# AuxTalon_LoadSwitch.net
KiCad netlist of a schematic drawn in EAGLE
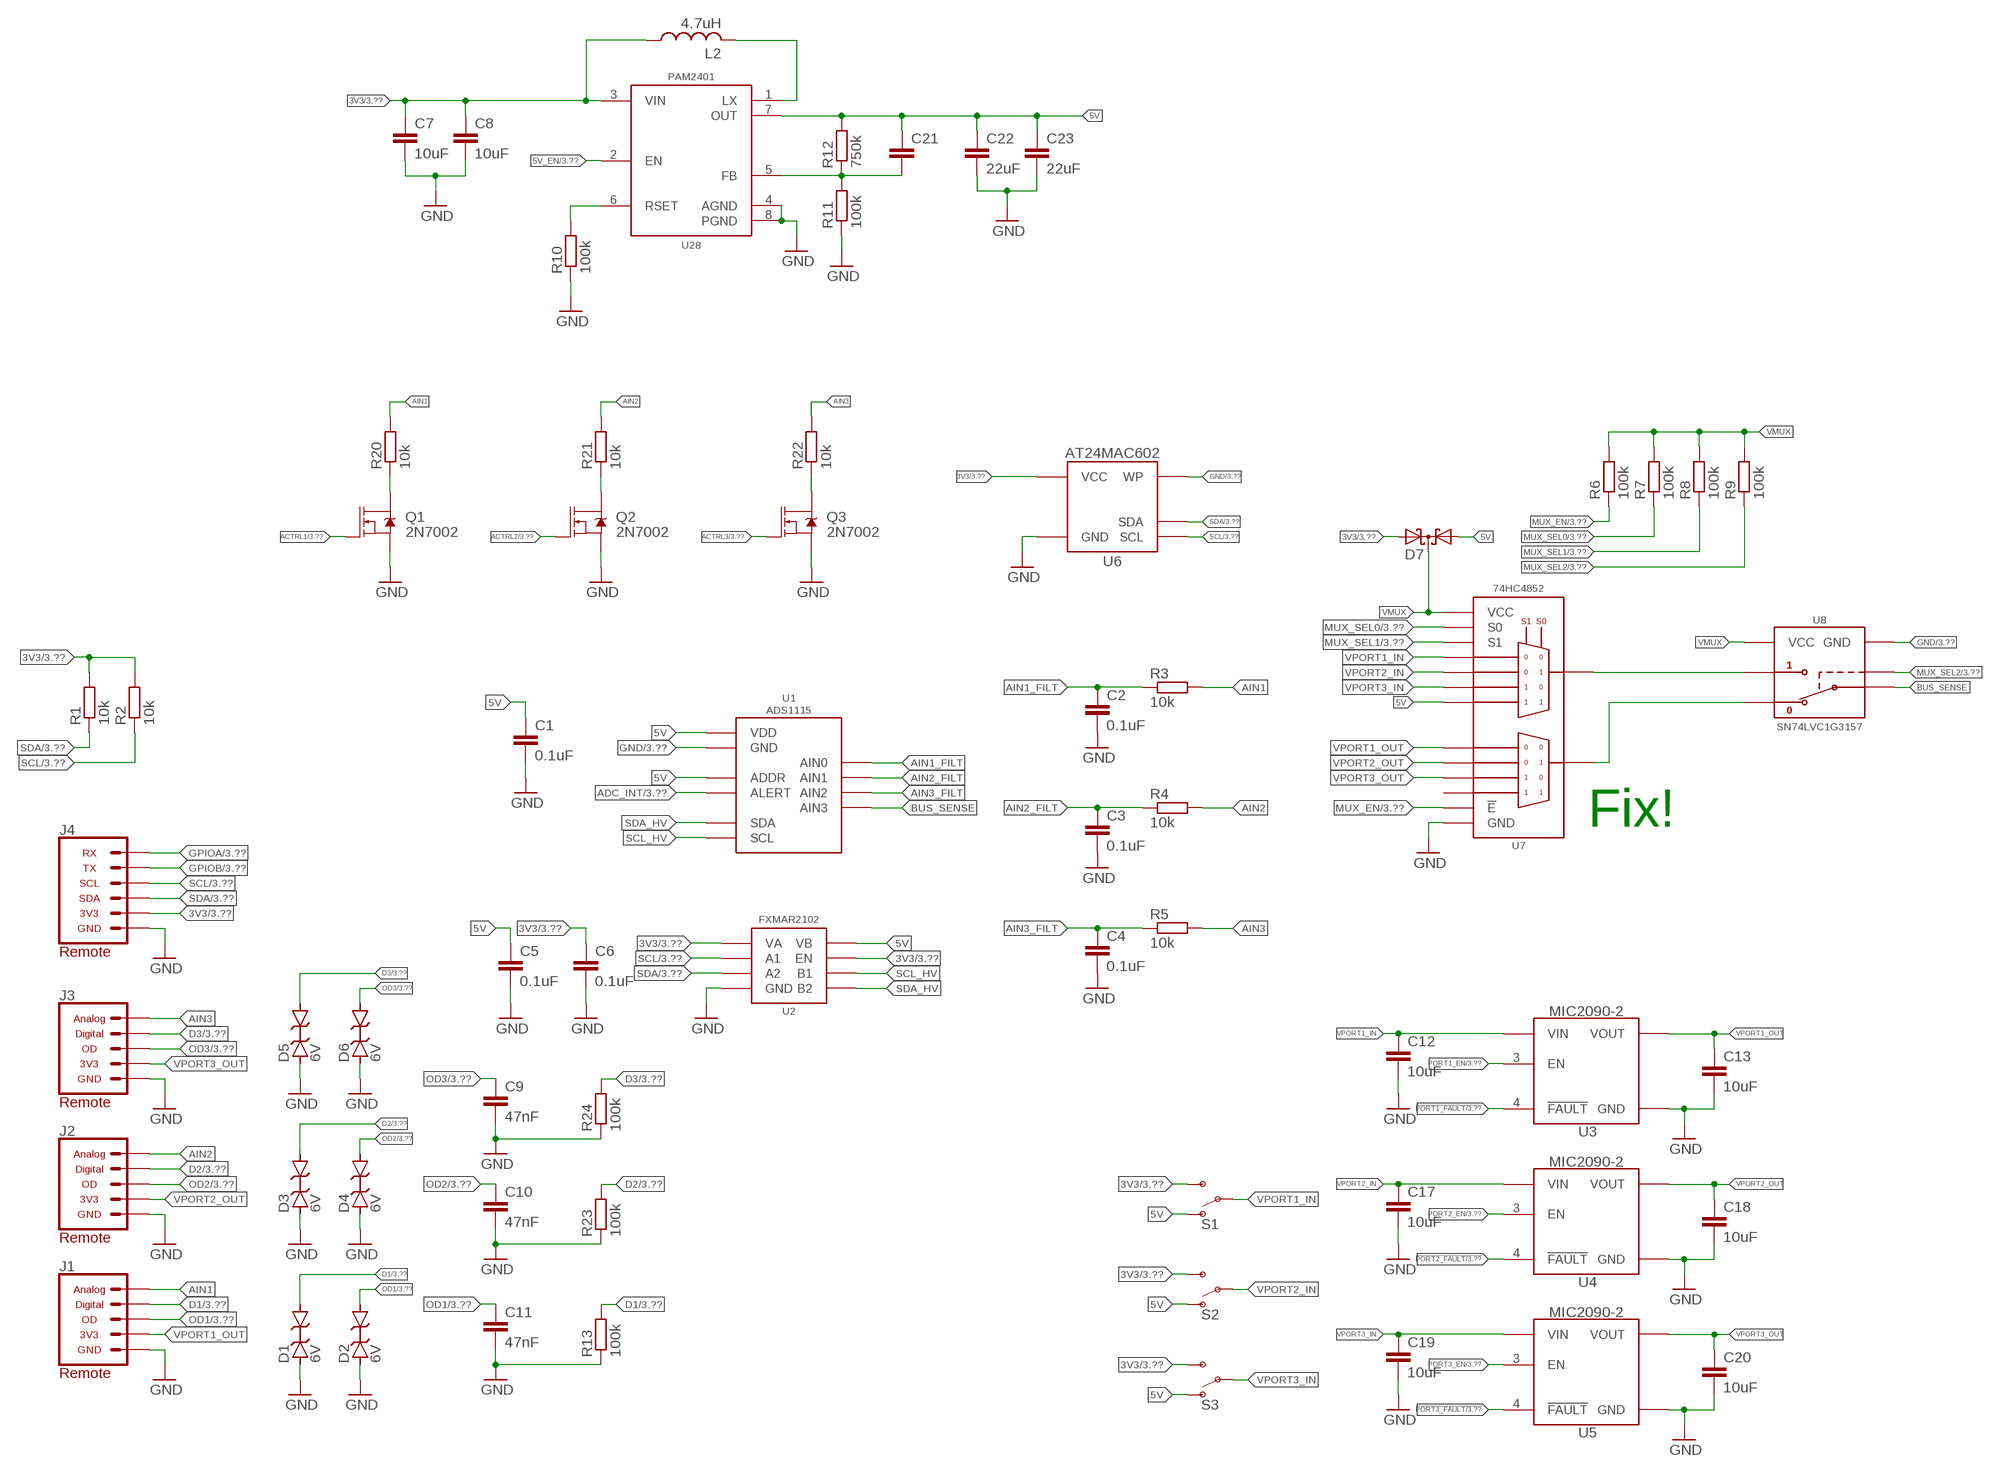
[diagram p0: schematic, sheet 2]
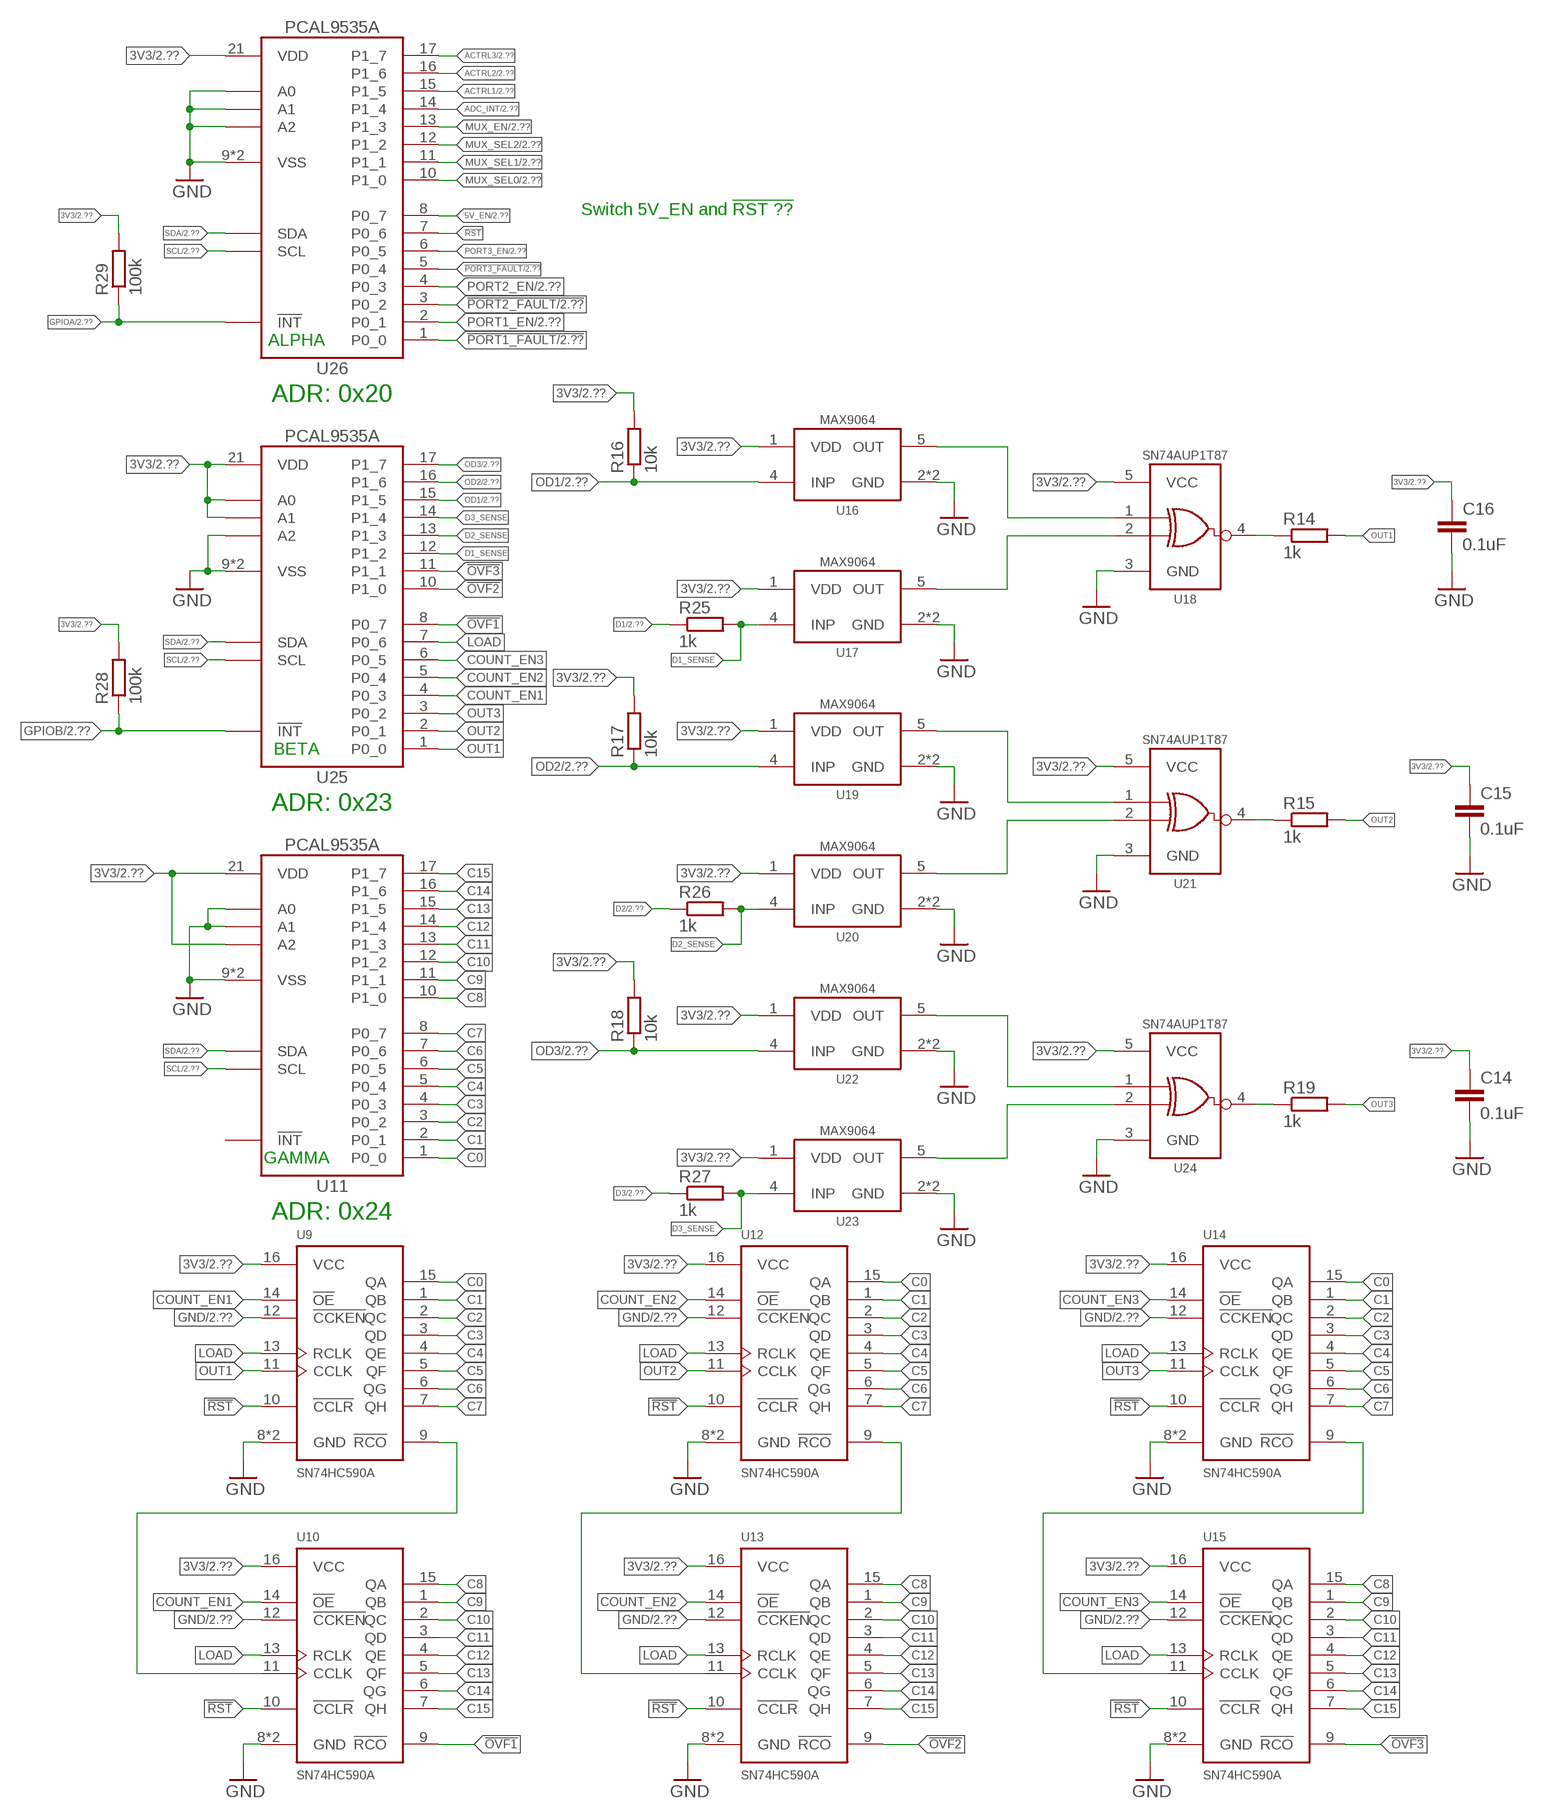
[diagram p1: schematic, sheet 3]

(export (version "E")
  (design (tool "Eeschema 10.0.6"))
  (components
    (comp (ref "C1")
      (value "0.1uF")
      (footprint "eagle-import:C0402")
      (fields (field (name "MF") "Murata") (field (name "MPN") "GCM155R71C104KA55D"))
      (libsource (lib "eagle-import") (part "C-EUC04020.1UF"))
    )
    (comp (ref "C2")
      (value "0.1uF")
      (footprint "eagle-import:C0805")
      (fields (field (name "MF") "Kemet") (field (name "MPN") "C0805C104M3RACTU"))
      (libsource (lib "eagle-import") (part "C-EUC08050.1UF"))
    )
    (comp (ref "C3")
      (value "0.1uF")
      (footprint "eagle-import:C0805")
      (fields (field (name "MF") "Kemet") (field (name "MPN") "C0805C104M3RACTU"))
      (libsource (lib "eagle-import") (part "C-EUC08050.1UF"))
    )
    (comp (ref "C4")
      (value "0.1uF")
      (footprint "eagle-import:C0805")
      (fields (field (name "MF") "Kemet") (field (name "MPN") "C0805C104M3RACTU"))
      (libsource (lib "eagle-import") (part "C-EUC08050.1UF"))
    )
    (comp (ref "C5")
      (value "0.1uF")
      (footprint "eagle-import:C0402")
      (fields (field (name "MF") "Murata") (field (name "MPN") "GCM155R71C104KA55D"))
      (libsource (lib "eagle-import") (part "C-EUC04020.1UF"))
    )
    (comp (ref "C6")
      (value "0.1uF")
      (footprint "eagle-import:C0402")
      (fields (field (name "MF") "Murata") (field (name "MPN") "GCM155R71C104KA55D"))
      (libsource (lib "eagle-import") (part "C-EUC04020.1UF"))
    )
    (comp (ref "C7")
      (value "10uF")
      (footprint "eagle-import:C0805")
      (fields (field (name "MF") "Murata") (field (name "MPN") "GRM21BR61C106KE15K"))
      (libsource (lib "eagle-import") (part "C-EUC080510UF"))
    )
    (comp (ref "C8")
      (value "10uF")
      (footprint "eagle-import:C0805")
      (fields (field (name "MF") "Murata") (field (name "MPN") "GRM21BR61C106KE15K"))
      (libsource (lib "eagle-import") (part "C-EUC080510UF"))
    )
    (comp (ref "C9")
      (value "47nF")
      (footprint "eagle-import:C0402")
      (fields (field (name "MF") "Murata") (field (name "MPN") "GRM155R71E473KA88D"))
      (libsource (lib "eagle-import") (part "C-EUC040247NF"))
    )
    (comp (ref "C10")
      (value "47nF")
      (footprint "eagle-import:C0402")
      (fields (field (name "MF") "Murata") (field (name "MPN") "GRM155R71E473KA88D"))
      (libsource (lib "eagle-import") (part "C-EUC040247NF"))
    )
    (comp (ref "C11")
      (value "47nF")
      (footprint "eagle-import:C0402")
      (fields (field (name "MF") "Murata") (field (name "MPN") "GRM155R71E473KA88D"))
      (libsource (lib "eagle-import") (part "C-EUC040247NF"))
    )
    (comp (ref "C12")
      (value "10uF")
      (footprint "eagle-import:C0805")
      (fields (field (name "MF") "Murata") (field (name "MPN") "GRM21BR61C106KE15K"))
      (libsource (lib "eagle-import") (part "C-EUC080510UF"))
    )
    (comp (ref "C13")
      (value "10uF")
      (footprint "eagle-import:C0603")
      (fields (field (name "MF") "Murata") (field (name "MPN") "GRM188R61C106KAALD"))
      (libsource (lib "eagle-import") (part "C-EUC060310UF"))
    )
    (comp (ref "C17")
      (value "10uF")
      (footprint "eagle-import:C0805")
      (fields (field (name "MF") "Murata") (field (name "MPN") "GRM21BR61C106KE15K"))
      (libsource (lib "eagle-import") (part "C-EUC080510UF"))
    )
    (comp (ref "C18")
      (value "10uF")
      (footprint "eagle-import:C0603")
      (fields (field (name "MF") "Murata") (field (name "MPN") "GRM188R61C106KAALD"))
      (libsource (lib "eagle-import") (part "C-EUC060310UF"))
    )
    (comp (ref "C19")
      (value "10uF")
      (footprint "eagle-import:C0805")
      (fields (field (name "MF") "Murata") (field (name "MPN") "GRM21BR61C106KE15K"))
      (libsource (lib "eagle-import") (part "C-EUC080510UF"))
    )
    (comp (ref "C20")
      (value "10uF")
      (footprint "eagle-import:C0603")
      (fields (field (name "MF") "Murata") (field (name "MPN") "GRM188R61C106KAALD"))
      (libsource (lib "eagle-import") (part "C-EUC060310UF"))
    )
    (comp (ref "C21")
      (value "C-EUC0402")
      (footprint "eagle-import:C0402")
      (fields (field (name "DIGIKEY") "DNP") (field (name "MF") "N/A") (field (name "MPN") "DNP"))
      (libsource (lib "eagle-import") (part "C-EUC0402"))
    )
    (comp (ref "C22")
      (value "22uF")
      (footprint "eagle-import:C0805")
      (fields (field (name "MF") "Murata") (field (name "MPN") "GRM219R61C226ME15L"))
      (libsource (lib "eagle-import") (part "C-EUC080522UF"))
    )
    (comp (ref "C23")
      (value "22uF")
      (footprint "eagle-import:C0805")
      (fields (field (name "MF") "Murata") (field (name "MPN") "GRM219R61C226ME15L"))
      (libsource (lib "eagle-import") (part "C-EUC080522UF"))
    )
    (comp (ref "D1")
      (value "6V")
      (footprint "eagle-import:D0402")
      (fields (field (name "MF") "Diodes Inc") (field (name "MPN") "D5V0L1B2LP4-7B"))
      (libsource (lib "eagle-import") (part "DIODE_ESD_BI_0402_D5V0L1"))
    )
    (comp (ref "D2")
      (value "6V")
      (footprint "eagle-import:D0402")
      (fields (field (name "MF") "Diodes Inc") (field (name "MPN") "D5V0L1B2LP4-7B"))
      (libsource (lib "eagle-import") (part "DIODE_ESD_BI_0402_D5V0L1"))
    )
    (comp (ref "D3")
      (value "6V")
      (footprint "eagle-import:D0402")
      (fields (field (name "MF") "Diodes Inc") (field (name "MPN") "D5V0L1B2LP4-7B"))
      (libsource (lib "eagle-import") (part "DIODE_ESD_BI_0402_D5V0L1"))
    )
    (comp (ref "D4")
      (value "6V")
      (footprint "eagle-import:D0402")
      (fields (field (name "MF") "Diodes Inc") (field (name "MPN") "D5V0L1B2LP4-7B"))
      (libsource (lib "eagle-import") (part "DIODE_ESD_BI_0402_D5V0L1"))
    )
    (comp (ref "D5")
      (value "6V")
      (footprint "eagle-import:D0402")
      (fields (field (name "MF") "Diodes Inc") (field (name "MPN") "D5V0L1B2LP4-7B"))
      (libsource (lib "eagle-import") (part "DIODE_ESD_BI_0402_D5V0L1"))
    )
    (comp (ref "D6")
      (value "6V")
      (footprint "eagle-import:D0402")
      (fields (field (name "MF") "Diodes Inc") (field (name "MPN") "D5V0L1B2LP4-7B"))
      (libsource (lib "eagle-import") (part "DIODE_ESD_BI_0402_D5V0L1"))
    )
    (comp (ref "D7")
      (value "DIODE_CCBAT54CSOT23")
      (footprint "eagle-import:SOT23-3")
      (fields (field (name "MF") "ON Semiconductor") (field (name "MPN") "BAT54CLT1G"))
      (libsource (lib "eagle-import") (part "DIODE_CCSOT23BAT54C"))
    )
    (comp (ref "J1")
      (value "CONN_AUX_M12_REMOTE")
      (footprint "eagle-import:1X05_M12_TE_T41410")
      (fields (field (name "DISP") "Remote") (field (name "MF") "TE") (field (name "MPN") "T4141012051-000"))
      (libsource (lib "eagle-import") (part "CONN_AUX_M12_REMOTE"))
    )
    (comp (ref "J2")
      (value "CONN_AUX_M12_REMOTE")
      (footprint "eagle-import:1X05_M12_TE_T41410")
      (fields (field (name "DISP") "Remote") (field (name "MF") "TE") (field (name "MPN") "T4141012051-000"))
      (libsource (lib "eagle-import") (part "CONN_AUX_M12_REMOTE"))
    )
    (comp (ref "J3")
      (value "CONN_AUX_M12_REMOTE")
      (footprint "eagle-import:1X05_M12_TE_T41410")
      (fields (field (name "DISP") "Remote") (field (name "MF") "TE") (field (name "MPN") "T4141012051-000"))
      (libsource (lib "eagle-import") (part "CONN_AUX_M12_REMOTE"))
    )
    (comp (ref "J4")
      (value "CONN_TALON_REMOTE")
      (footprint "eagle-import:1X06_MICROLOCKPLUS")
      (fields (field (name "DISP") "Remote") (field (name "MF") "Molex") (field (name "MPN") "2059570671"))
      (libsource (lib "eagle-import") (part "CONN_TALON_REMOTE"))
    )
    (comp (ref "L2")
      (value "4.7uH")
      (footprint "eagle-import:WE-MAPI(2.5X2)")
      (fields (field (name "MF") "Wurth") (field (name "MPN") "74438323047"))
      (libsource (lib "eagle-import") (part "INDUCTOR_MAPI_2.5X2"))
    )
    (comp (ref "Q1")
      (value "2N7002")
      (footprint "eagle-import:SOT23-3")
      (fields (field (name "MF") "Nexperia") (field (name "MPN") "2N7002P,215"))
      (libsource (lib "eagle-import") (part "MOSFET-NCH-2N7002P"))
    )
    (comp (ref "Q2")
      (value "2N7002")
      (footprint "eagle-import:SOT23-3")
      (fields (field (name "MF") "Nexperia") (field (name "MPN") "2N7002P,215"))
      (libsource (lib "eagle-import") (part "MOSFET-NCH-2N7002P"))
    )
    (comp (ref "Q3")
      (value "2N7002")
      (footprint "eagle-import:SOT23-3")
      (fields (field (name "MF") "Nexperia") (field (name "MPN") "2N7002P,215"))
      (libsource (lib "eagle-import") (part "MOSFET-NCH-2N7002P"))
    )
    (comp (ref "R1")
      (value "10k")
      (footprint "eagle-import:R0402")
      (fields (field (name "MF") "Yageo") (field (name "MPN") "RC0402FR-0710KL"))
      (libsource (lib "eagle-import") (part "R-EU_R040210K"))
    )
    (comp (ref "R2")
      (value "10k")
      (footprint "eagle-import:R0402")
      (fields (field (name "MF") "Yageo") (field (name "MPN") "RC0402FR-0710KL"))
      (libsource (lib "eagle-import") (part "R-EU_R040210K"))
    )
    (comp (ref "R3")
      (value "10k")
      (footprint "eagle-import:R0402")
      (fields (field (name "MF") "Yageo") (field (name "MPN") "RC0402FR-0710KL"))
      (libsource (lib "eagle-import") (part "R-EU_R040210K"))
    )
    (comp (ref "R4")
      (value "10k")
      (footprint "eagle-import:R0402")
      (fields (field (name "MF") "Yageo") (field (name "MPN") "RC0402FR-0710KL"))
      (libsource (lib "eagle-import") (part "R-EU_R040210K"))
    )
    (comp (ref "R5")
      (value "10k")
      (footprint "eagle-import:R0402")
      (fields (field (name "MF") "Yageo") (field (name "MPN") "RC0402FR-0710KL"))
      (libsource (lib "eagle-import") (part "R-EU_R040210K"))
    )
    (comp (ref "R6")
      (value "100k")
      (footprint "eagle-import:R0402")
      (fields (field (name "MF") "Yageo") (field (name "MPN") "RC0402FR-07100KL"))
      (libsource (lib "eagle-import") (part "R-EU_R0402100K"))
    )
    (comp (ref "R7")
      (value "100k")
      (footprint "eagle-import:R0402")
      (fields (field (name "MF") "Yageo") (field (name "MPN") "RC0402FR-07100KL"))
      (libsource (lib "eagle-import") (part "R-EU_R0402100K"))
    )
    (comp (ref "R8")
      (value "100k")
      (footprint "eagle-import:R0402")
      (fields (field (name "MF") "Yageo") (field (name "MPN") "RC0402FR-07100KL"))
      (libsource (lib "eagle-import") (part "R-EU_R0402100K"))
    )
    (comp (ref "R9")
      (value "100k")
      (footprint "eagle-import:R0402")
      (fields (field (name "MF") "Yageo") (field (name "MPN") "RC0402FR-07100KL"))
      (libsource (lib "eagle-import") (part "R-EU_R0402100K"))
    )
    (comp (ref "R10")
      (value "100k")
      (footprint "eagle-import:R0603")
      (fields (field (name "MF") "Yageo") (field (name "MPN") "RC0603FR-07100KL"))
      (libsource (lib "eagle-import") (part "R-EU_R0603100K"))
    )
    (comp (ref "R11")
      (value "100k")
      (footprint "eagle-import:R0603")
      (fields (field (name "MF") "Yageo") (field (name "MPN") "RC0603FR-07100KL"))
      (libsource (lib "eagle-import") (part "R-EU_R0603100K"))
    )
    (comp (ref "R12")
      (value "750k")
      (footprint "eagle-import:R0603")
      (fields (field (name "MF") "Yageo") (field (name "MPN") "RC0603FR-07750KL"))
      (libsource (lib "eagle-import") (part "R-EU_R0603750K"))
    )
    (comp (ref "R13")
      (value "100k")
      (footprint "eagle-import:R0402")
      (fields (field (name "MF") "Yageo") (field (name "MPN") "RC0402FR-07100KL"))
      (libsource (lib "eagle-import") (part "R-EU_R0402100K"))
    )
    (comp (ref "R20")
      (value "10k")
      (footprint "eagle-import:R0402")
      (fields (field (name "MF") "Yageo") (field (name "MPN") "RC0402FR-0710KL"))
      (libsource (lib "eagle-import") (part "R-EU_R040210K"))
    )
    (comp (ref "R21")
      (value "10k")
      (footprint "eagle-import:R0402")
      (fields (field (name "MF") "Yageo") (field (name "MPN") "RC0402FR-0710KL"))
      (libsource (lib "eagle-import") (part "R-EU_R040210K"))
    )
    (comp (ref "R22")
      (value "10k")
      (footprint "eagle-import:R0402")
      (fields (field (name "MF") "Yageo") (field (name "MPN") "RC0402FR-0710KL"))
      (libsource (lib "eagle-import") (part "R-EU_R040210K"))
    )
    (comp (ref "R23")
      (value "100k")
      (footprint "eagle-import:R0402")
      (fields (field (name "MF") "Yageo") (field (name "MPN") "RC0402FR-07100KL"))
      (libsource (lib "eagle-import") (part "R-EU_R0402100K"))
    )
    (comp (ref "R24")
      (value "100k")
      (footprint "eagle-import:R0402")
      (fields (field (name "MF") "Yageo") (field (name "MPN") "RC0402FR-07100KL"))
      (libsource (lib "eagle-import") (part "R-EU_R0402100K"))
    )
    (comp (ref "S1")
      (value "SPDTCAS-120A1")
      (footprint "eagle-import:CAS-120A1")
      (fields (field (name "MF") "Nidec Copal") (field (name "MPN") "CAS-120TA"))
      (libsource (lib "eagle-import") (part "SPDTCAS-120A1"))
    )
    (comp (ref "S2")
      (value "SPDTCAS-120A1")
      (footprint "eagle-import:CAS-120A1")
      (fields (field (name "MF") "Nidec Copal") (field (name "MPN") "CAS-120TA"))
      (libsource (lib "eagle-import") (part "SPDTCAS-120A1"))
    )
    (comp (ref "S3")
      (value "SPDTCAS-120A1")
      (footprint "eagle-import:CAS-120A1")
      (fields (field (name "MF") "Nidec Copal") (field (name "MPN") "CAS-120TA"))
      (libsource (lib "eagle-import") (part "SPDTCAS-120A1"))
    )
    (comp (ref "U1")
      (value "ADS1115")
      (footprint "eagle-import:VSSOP_10")
      (fields (field (name "MF") "TI") (field (name "MPN") "ADS1115IDGSR"))
      (libsource (lib "eagle-import") (part "ADS1115"))
    )
    (comp (ref "U2")
      (value "FXMAR2102UMLP")
      (footprint "eagle-import:UQFN-8_1.4X1.2")
      (fields
        (field (name "DISP") "FXMAR2102")
        (field (name "MF") "OnSemi")
        (field (name "MPN") "FXMAR2102UMX-F106")
      )
      (libsource (lib "eagle-import") (part "FXMAR2102UMLP"))
    )
    (comp (ref "U3")
      (value "MIC2090-2")
      (footprint "eagle-import:SOT23-5")
      (fields
        (field (name "DISP") "MIC2090-2")
        (field (name "MF") "Microchip")
        (field (name "MPN") "MIC2090-2YM5-TR")
      )
      (libsource (lib "eagle-import") (part "MIC2090-2"))
    )
    (comp (ref "U4")
      (value "MIC2090-2")
      (footprint "eagle-import:SOT23-5")
      (fields
        (field (name "DISP") "MIC2090-2")
        (field (name "MF") "Microchip")
        (field (name "MPN") "MIC2090-2YM5-TR")
      )
      (libsource (lib "eagle-import") (part "MIC2090-2"))
    )
    (comp (ref "U5")
      (value "MIC2090-2")
      (footprint "eagle-import:SOT23-5")
      (fields
        (field (name "DISP") "MIC2090-2")
        (field (name "MF") "Microchip")
        (field (name "MPN") "MIC2090-2YM5-TR")
      )
      (libsource (lib "eagle-import") (part "MIC2090-2"))
    )
    (comp (ref "U6")
      (value "AT24MAC602SOT23")
      (footprint "eagle-import:SOT23-5")
      (fields
        (field (name "DISP") "AT24MAC602")
        (field (name "MF") "Microchip")
        (field (name "MPN") "AT24MAC602-STUM-T")
      )
      (libsource (lib "eagle-import") (part "AT24MAC02SOT236"))
    )
    (comp (ref "U7")
      (value "74HC4852")
      (footprint "eagle-import:VQFN-16")
      (fields
        (field (name "DISP") "74HC4852")
        (field (name "MF") "Nexperia")
        (field (name "MPN") "74HC4852BQ-Q100,11")
      )
      (libsource (lib "eagle-import") (part "74HC4852"))
    )
    (comp (ref "U8")
      (value "SN74LVC1G3157SC70")
      (footprint "eagle-import:DCK_R-PDSO-G6")
      (fields
        (field (name "DISP") "SN74LVC1G3157")
        (field (name "MF") "TI")
        (field (name "MPN") "SN74LVC1G3157DCKR")
      )
      (libsource (lib "eagle-import") (part "SN74LVC1G3157SC70"))
    )
    (comp (ref "U28")
      (value "PAM2401MSOP")
      (footprint "eagle-import:MSOP_8")
      (fields (field (name "MF") "Diodes Inc") (field (name "MPN") "PAM2401SCADJ"))
      (libsource (lib "eagle-import") (part "PAM2401MSOP"))
    )
    (comp (ref "C14")
      (value "0.1uF")
      (footprint "eagle-import:C0402")
      (fields (field (name "MF") "Murata") (field (name "MPN") "GCM155R71C104KA55D"))
      (libsource (lib "eagle-import") (part "C-EUC04020.1UF"))
    )
    (comp (ref "C15")
      (value "0.1uF")
      (footprint "eagle-import:C0402")
      (fields (field (name "MF") "Murata") (field (name "MPN") "GCM155R71C104KA55D"))
      (libsource (lib "eagle-import") (part "C-EUC04020.1UF"))
    )
    (comp (ref "C16")
      (value "0.1uF")
      (footprint "eagle-import:C0402")
      (fields (field (name "MF") "Murata") (field (name "MPN") "GCM155R71C104KA55D"))
      (libsource (lib "eagle-import") (part "C-EUC04020.1UF"))
    )
    (comp (ref "R14")
      (value "1k")
      (footprint "eagle-import:R0402")
      (fields (field (name "MF") "Yageo") (field (name "MPN") "RC0402FR-071KL"))
      (libsource (lib "eagle-import") (part "R-EU_R04021K"))
    )
    (comp (ref "R15")
      (value "1k")
      (footprint "eagle-import:R0402")
      (fields (field (name "MF") "Yageo") (field (name "MPN") "RC0402FR-071KL"))
      (libsource (lib "eagle-import") (part "R-EU_R04021K"))
    )
    (comp (ref "R16")
      (value "10k")
      (footprint "eagle-import:R0402")
      (fields (field (name "MF") "Yageo") (field (name "MPN") "RC0402FR-0710KL"))
      (libsource (lib "eagle-import") (part "R-EU_R040210K"))
    )
    (comp (ref "R17")
      (value "10k")
      (footprint "eagle-import:R0402")
      (fields (field (name "MF") "Yageo") (field (name "MPN") "RC0402FR-0710KL"))
      (libsource (lib "eagle-import") (part "R-EU_R040210K"))
    )
    (comp (ref "R18")
      (value "10k")
      (footprint "eagle-import:R0402")
      (fields (field (name "MF") "Yageo") (field (name "MPN") "RC0402FR-0710KL"))
      (libsource (lib "eagle-import") (part "R-EU_R040210K"))
    )
    (comp (ref "R19")
      (value "1k")
      (footprint "eagle-import:R0402")
      (fields (field (name "MF") "Yageo") (field (name "MPN") "RC0402FR-071KL"))
      (libsource (lib "eagle-import") (part "R-EU_R04021K"))
    )
    (comp (ref "R25")
      (value "1k")
      (footprint "eagle-import:R0402")
      (fields (field (name "MF") "Yageo") (field (name "MPN") "RC0402FR-071KL"))
      (libsource (lib "eagle-import") (part "R-EU_R04021K"))
    )
    (comp (ref "R26")
      (value "1k")
      (footprint "eagle-import:R0402")
      (fields (field (name "MF") "Yageo") (field (name "MPN") "RC0402FR-071KL"))
      (libsource (lib "eagle-import") (part "R-EU_R04021K"))
    )
    (comp (ref "R27")
      (value "1k")
      (footprint "eagle-import:R0402")
      (fields (field (name "MF") "Yageo") (field (name "MPN") "RC0402FR-071KL"))
      (libsource (lib "eagle-import") (part "R-EU_R04021K"))
    )
    (comp (ref "R28")
      (value "100k")
      (footprint "eagle-import:R0402")
      (fields (field (name "MF") "Yageo") (field (name "MPN") "RC0402FR-07100KL"))
      (libsource (lib "eagle-import") (part "R-EU_R0402100K"))
    )
    (comp (ref "R29")
      (value "100k")
      (footprint "eagle-import:R0402")
      (fields (field (name "MF") "Yageo") (field (name "MPN") "RC0402FR-07100KL"))
      (libsource (lib "eagle-import") (part "R-EU_R0402100K"))
    )
    (comp (ref "U9")
      (value "SN74HC590AVQFN")
      (footprint "eagle-import:VQFN-16")
      (fields (field (name "MF") "Nexperia") (field (name "MPN") "74HC590BQ,115"))
      (libsource (lib "eagle-import") (part "SN74HC590AVQFN"))
    )
    (comp (ref "U10")
      (value "SN74HC590AVQFN")
      (footprint "eagle-import:VQFN-16")
      (fields (field (name "MF") "Nexperia") (field (name "MPN") "74HC590BQ,115"))
      (libsource (lib "eagle-import") (part "SN74HC590AVQFN"))
    )
    (comp (ref "U11")
      (value "PCAL9535AQFN")
      (footprint "eagle-import:QFN24")
      (fields
        (field (name "DISP") "PCAL9535A")
        (field (name "MF") "NXP")
        (field (name "MPN") "PCAL9535AHF,128")
      )
      (libsource (lib "eagle-import") (part "PCAL955AQFN3"))
    )
    (comp (ref "U12")
      (value "SN74HC590AVQFN")
      (footprint "eagle-import:VQFN-16")
      (fields (field (name "MF") "Nexperia") (field (name "MPN") "74HC590BQ,115"))
      (libsource (lib "eagle-import") (part "SN74HC590AVQFN"))
    )
    (comp (ref "U13")
      (value "SN74HC590AVQFN")
      (footprint "eagle-import:VQFN-16")
      (fields (field (name "MF") "Nexperia") (field (name "MPN") "74HC590BQ,115"))
      (libsource (lib "eagle-import") (part "SN74HC590AVQFN"))
    )
    (comp (ref "U14")
      (value "SN74HC590AVQFN")
      (footprint "eagle-import:VQFN-16")
      (fields (field (name "MF") "Nexperia") (field (name "MPN") "74HC590BQ,115"))
      (libsource (lib "eagle-import") (part "SN74HC590AVQFN"))
    )
    (comp (ref "U15")
      (value "SN74HC590AVQFN")
      (footprint "eagle-import:VQFN-16")
      (fields (field (name "MF") "Nexperia") (field (name "MPN") "74HC590BQ,115"))
      (libsource (lib "eagle-import") (part "SN74HC590AVQFN"))
    )
    (comp (ref "U16")
      (value "MAX9064")
      (footprint "eagle-import:SOT23-5")
      (fields (field (name "DISP") "MAX9064") (field (name "MF") "Maxim") (field (name "MPN") "MAX9064EUK+T"))
      (libsource (lib "eagle-import") (part "MAX9064"))
    )
    (comp (ref "U17")
      (value "MAX9064")
      (footprint "eagle-import:SOT23-5")
      (fields (field (name "DISP") "MAX9064") (field (name "MF") "Maxim") (field (name "MPN") "MAX9064EUK+T"))
      (libsource (lib "eagle-import") (part "MAX9064"))
    )
    (comp (ref "U18")
      (value "SN74AUP1T87")
      (footprint "eagle-import:DCK_R-PDSO-G5")
      (fields
        (field (name "DISP") "SN74AUP1T87")
        (field (name "MF") "TI")
        (field (name "MPN") "SN74AUP1T87DCKR")
      )
      (libsource (lib "eagle-import") (part "SN74AUP1T87"))
    )
    (comp (ref "U19")
      (value "MAX9064")
      (footprint "eagle-import:SOT23-5")
      (fields (field (name "DISP") "MAX9064") (field (name "MF") "Maxim") (field (name "MPN") "MAX9064EUK+T"))
      (libsource (lib "eagle-import") (part "MAX9064"))
    )
    (comp (ref "U20")
      (value "MAX9064")
      (footprint "eagle-import:SOT23-5")
      (fields (field (name "DISP") "MAX9064") (field (name "MF") "Maxim") (field (name "MPN") "MAX9064EUK+T"))
      (libsource (lib "eagle-import") (part "MAX9064"))
    )
    (comp (ref "U21")
      (value "SN74AUP1T87")
      (footprint "eagle-import:DCK_R-PDSO-G5")
      (fields
        (field (name "DISP") "SN74AUP1T87")
        (field (name "MF") "TI")
        (field (name "MPN") "SN74AUP1T87DCKR")
      )
      (libsource (lib "eagle-import") (part "SN74AUP1T87"))
    )
    (comp (ref "U22")
      (value "MAX9064")
      (footprint "eagle-import:SOT23-5")
      (fields (field (name "DISP") "MAX9064") (field (name "MF") "Maxim") (field (name "MPN") "MAX9064EUK+T"))
      (libsource (lib "eagle-import") (part "MAX9064"))
    )
    (comp (ref "U23")
      (value "MAX9064")
      (footprint "eagle-import:SOT23-5")
      (fields (field (name "DISP") "MAX9064") (field (name "MF") "Maxim") (field (name "MPN") "MAX9064EUK+T"))
      (libsource (lib "eagle-import") (part "MAX9064"))
    )
    (comp (ref "U24")
      (value "SN74AUP1T87")
      (footprint "eagle-import:DCK_R-PDSO-G5")
      (fields
        (field (name "DISP") "SN74AUP1T87")
        (field (name "MF") "TI")
        (field (name "MPN") "SN74AUP1T87DCKR")
      )
      (libsource (lib "eagle-import") (part "SN74AUP1T87"))
    )
    (comp (ref "U25")
      (value "PCAL9535AQFN")
      (footprint "eagle-import:QFN24")
      (fields
        (field (name "DISP") "PCAL9535A")
        (field (name "MF") "NXP")
        (field (name "MPN") "PCAL9535AHF,128")
      )
      (libsource (lib "eagle-import") (part "PCAL955AQFN3"))
    )
    (comp (ref "U26")
      (value "PCAL9535AQFN")
      (footprint "eagle-import:QFN24")
      (fields
        (field (name "DISP") "PCAL9535A")
        (field (name "MF") "NXP")
        (field (name "MPN") "PCAL9535AHF,128")
      )
      (libsource (lib "eagle-import") (part "PCAL955AQFN3"))
    )
  )
  (nets
    (net (code "1") (name "3V3") (class "Default")
      (node (ref "C14") (pin "1") (pinfunction "1_1") (pintype "passive"))
      (node (ref "C15") (pin "1") (pinfunction "1_1") (pintype "passive"))
      (node (ref "C16") (pin "1") (pinfunction "1_1") (pintype "passive"))
      (node (ref "C6") (pin "1") (pinfunction "1_1") (pintype "passive"))
      (node (ref "C7") (pin "1") (pinfunction "1_1") (pintype "passive"))
      (node (ref "C8") (pin "1") (pinfunction "1_1") (pintype "passive"))
      (node (ref "D7") (pin "2") (pinfunction "A2_2") (pintype "passive"))
      (node (ref "J4") (pin "2") (pinfunction "3V3_2") (pintype "passive"))
      (node (ref "L2") (pin "P$1") (pinfunction "1_P$1") (pintype "passive"))
      (node (ref "R1") (pin "2") (pinfunction "2_2") (pintype "passive"))
      (node (ref "R16") (pin "2") (pinfunction "2_2") (pintype "passive"))
      (node (ref "R17") (pin "2") (pinfunction "2_2") (pintype "passive"))
      (node (ref "R18") (pin "2") (pinfunction "2_2") (pintype "passive"))
      (node (ref "R2") (pin "2") (pinfunction "2_2") (pintype "passive"))
      (node (ref "R28") (pin "2") (pinfunction "2_2") (pintype "passive"))
      (node (ref "R29") (pin "2") (pinfunction "2_2") (pintype "passive"))
      (node (ref "S1") (pin "3") (pinfunction "S_3") (pintype "passive"))
      (node (ref "S2") (pin "3") (pinfunction "S_3") (pintype "passive"))
      (node (ref "S3") (pin "3") (pinfunction "S_3") (pintype "passive"))
      (node (ref "U10") (pin "16") (pinfunction "VCC_16") (pintype "power_in"))
      (node (ref "U11") (pin "21") (pinfunction "VDD_21") (pintype "power_in"))
      (node (ref "U11") (pin "24") (pinfunction "A2_24") (pintype "input"))
      (node (ref "U12") (pin "16") (pinfunction "VCC_16") (pintype "power_in"))
      (node (ref "U13") (pin "16") (pinfunction "VCC_16") (pintype "power_in"))
      (node (ref "U14") (pin "16") (pinfunction "VCC_16") (pintype "power_in"))
      (node (ref "U15") (pin "16") (pinfunction "VCC_16") (pintype "power_in"))
      (node (ref "U16") (pin "1") (pinfunction "VDD_1") (pintype "power_in"))
      (node (ref "U17") (pin "1") (pinfunction "VDD_1") (pintype "power_in"))
      (node (ref "U18") (pin "5") (pinfunction "VCC_5") (pintype "power_in"))
      (node (ref "U19") (pin "1") (pinfunction "VDD_1") (pintype "power_in"))
      (node (ref "U2") (pin "1") (pinfunction "VA_1") (pintype "power_in"))
      (node (ref "U2") (pin "5") (pinfunction "EN_5") (pintype "input"))
      (node (ref "U20") (pin "1") (pinfunction "VDD_1") (pintype "power_in"))
      (node (ref "U21") (pin "5") (pinfunction "VCC_5") (pintype "power_in"))
      (node (ref "U22") (pin "1") (pinfunction "VDD_1") (pintype "power_in"))
      (node (ref "U23") (pin "1") (pinfunction "VDD_1") (pintype "power_in"))
      (node (ref "U24") (pin "5") (pinfunction "VCC_5") (pintype "power_in"))
      (node (ref "U25") (pin "18") (pinfunction "A0_18") (pintype "input"))
      (node (ref "U25") (pin "21") (pinfunction "VDD_21") (pintype "power_in"))
      (node (ref "U25") (pin "23") (pinfunction "A1_23") (pintype "input"))
      (node (ref "U26") (pin "21") (pinfunction "VDD_21") (pintype "power_in"))
      (node (ref "U28") (pin "3") (pinfunction "VIN_3") (pintype "power_in"))
      (node (ref "U6") (pin "4") (pinfunction "VCC_4") (pintype "power_in"))
      (node (ref "U9") (pin "16") (pinfunction "VCC_16") (pintype "power_in"))
    )
    (net (code "2") (name "5V") (class "Default")
      (node (ref "C1") (pin "1") (pinfunction "1_1") (pintype "passive"))
      (node (ref "C21") (pin "1") (pinfunction "1_1") (pintype "passive"))
      (node (ref "C22") (pin "1") (pinfunction "1_1") (pintype "passive"))
      (node (ref "C23") (pin "1") (pinfunction "1_1") (pintype "passive"))
      (node (ref "C5") (pin "1") (pinfunction "1_1") (pintype "passive"))
      (node (ref "D7") (pin "1") (pinfunction "A1_1") (pintype "passive"))
      (node (ref "R12") (pin "2") (pinfunction "2_2") (pintype "passive"))
      (node (ref "S1") (pin "1") (pinfunction "O_1") (pintype "passive"))
      (node (ref "S2") (pin "1") (pinfunction "O_1") (pintype "passive"))
      (node (ref "S3") (pin "1") (pinfunction "O_1") (pintype "passive"))
      (node (ref "U1") (pin "1") (pinfunction "ADDR_1") (pintype "bidirectional"))
      (node (ref "U1") (pin "8") (pinfunction "VDD_8") (pintype "power_in"))
      (node (ref "U2") (pin "8") (pinfunction "VB_8") (pintype "power_in"))
      (node (ref "U28") (pin "7") (pinfunction "OUT_7") (pintype "power_in"))
      (node (ref "U7") (pin "11") (pinfunction "1Y3_11") (pintype "input"))
    )
    (net (code "3") (name "5V_EN") (class "Default")
      (node (ref "U26") (pin "8") (pinfunction "P0_7_8") (pintype "bidirectional"))
      (node (ref "U28") (pin "2") (pinfunction "EN_2") (pintype "input"))
    )
    (net (code "4") (name "ACTRL1") (class "Default")
      (node (ref "Q1") (pin "1") (pinfunction "G_1") (pintype "bidirectional"))
      (node (ref "U26") (pin "15") (pinfunction "P1_5_15") (pintype "bidirectional"))
    )
    (net (code "5") (name "ACTRL2") (class "Default")
      (node (ref "Q2") (pin "1") (pinfunction "G_1") (pintype "bidirectional"))
      (node (ref "U26") (pin "16") (pinfunction "P1_6_16") (pintype "bidirectional"))
    )
    (net (code "6") (name "ACTRL3") (class "Default")
      (node (ref "Q3") (pin "1") (pinfunction "G_1") (pintype "bidirectional"))
      (node (ref "U26") (pin "17") (pinfunction "P1_7_17") (pintype "bidirectional"))
    )
    (net (code "7") (name "ADC_INT") (class "Default")
      (node (ref "U1") (pin "2") (pinfunction "ALERT_2") (pintype "bidirectional"))
      (node (ref "U26") (pin "14") (pinfunction "P1_4_14") (pintype "bidirectional"))
    )
    (net (code "8") (name "AIN1") (class "Default")
      (node (ref "J1") (pin "4") (pinfunction "ANALOG_4") (pintype "passive"))
      (node (ref "R20") (pin "2") (pinfunction "2_2") (pintype "passive"))
      (node (ref "R3") (pin "2") (pinfunction "2_2") (pintype "passive"))
    )
    (net (code "9") (name "AIN1_FILT") (class "Default")
      (node (ref "C2") (pin "1") (pinfunction "1_1") (pintype "passive"))
      (node (ref "R3") (pin "1") (pinfunction "1_1") (pintype "passive"))
      (node (ref "U1") (pin "4") (pinfunction "AIN0_4") (pintype "input"))
    )
    (net (code "10") (name "AIN2") (class "Default")
      (node (ref "J2") (pin "4") (pinfunction "ANALOG_4") (pintype "passive"))
      (node (ref "R21") (pin "2") (pinfunction "2_2") (pintype "passive"))
      (node (ref "R4") (pin "2") (pinfunction "2_2") (pintype "passive"))
    )
    (net (code "11") (name "AIN2_FILT") (class "Default")
      (node (ref "C3") (pin "1") (pinfunction "1_1") (pintype "passive"))
      (node (ref "R4") (pin "1") (pinfunction "1_1") (pintype "passive"))
      (node (ref "U1") (pin "5") (pinfunction "AIN1_5") (pintype "input"))
    )
    (net (code "12") (name "AIN3") (class "Default")
      (node (ref "J3") (pin "4") (pinfunction "ANALOG_4") (pintype "passive"))
      (node (ref "R22") (pin "2") (pinfunction "2_2") (pintype "passive"))
      (node (ref "R5") (pin "2") (pinfunction "2_2") (pintype "passive"))
    )
    (net (code "13") (name "AIN3_FILT") (class "Default")
      (node (ref "C4") (pin "1") (pinfunction "1_1") (pintype "passive"))
      (node (ref "R5") (pin "1") (pinfunction "1_1") (pintype "passive"))
      (node (ref "U1") (pin "6") (pinfunction "AIN2_6") (pintype "input"))
    )
    (net (code "14") (name "BUS_SENSE") (class "Default")
      (node (ref "U1") (pin "7") (pinfunction "AIN3_7") (pintype "input"))
      (node (ref "U8") (pin "4") (pinfunction "A_4") (pintype "bidirectional"))
    )
    (net (code "15") (name "C0") (class "Default")
      (node (ref "U11") (pin "1") (pinfunction "P0_0_1") (pintype "bidirectional"))
      (node (ref "U12") (pin "15") (pinfunction "QA_15") (pintype "output"))
      (node (ref "U14") (pin "15") (pinfunction "QA_15") (pintype "output"))
      (node (ref "U9") (pin "15") (pinfunction "QA_15") (pintype "output"))
    )
    (net (code "16") (name "C1") (class "Default")
      (node (ref "U11") (pin "2") (pinfunction "P0_1_2") (pintype "bidirectional"))
      (node (ref "U12") (pin "1") (pinfunction "QB_1") (pintype "output"))
      (node (ref "U14") (pin "1") (pinfunction "QB_1") (pintype "output"))
      (node (ref "U9") (pin "1") (pinfunction "QB_1") (pintype "output"))
    )
    (net (code "17") (name "C2") (class "Default")
      (node (ref "U11") (pin "3") (pinfunction "P0_2_3") (pintype "bidirectional"))
      (node (ref "U12") (pin "2") (pinfunction "QC_2") (pintype "output"))
      (node (ref "U14") (pin "2") (pinfunction "QC_2") (pintype "output"))
      (node (ref "U9") (pin "2") (pinfunction "QC_2") (pintype "output"))
    )
    (net (code "18") (name "C3") (class "Default")
      (node (ref "U11") (pin "4") (pinfunction "P0_3_4") (pintype "bidirectional"))
      (node (ref "U12") (pin "3") (pinfunction "QD_3") (pintype "output"))
      (node (ref "U14") (pin "3") (pinfunction "QD_3") (pintype "output"))
      (node (ref "U9") (pin "3") (pinfunction "QD_3") (pintype "output"))
    )
    (net (code "19") (name "C4") (class "Default")
      (node (ref "U11") (pin "5") (pinfunction "P0_4_5") (pintype "bidirectional"))
      (node (ref "U12") (pin "4") (pinfunction "QE_4") (pintype "output"))
      (node (ref "U14") (pin "4") (pinfunction "QE_4") (pintype "output"))
      (node (ref "U9") (pin "4") (pinfunction "QE_4") (pintype "output"))
    )
    (net (code "20") (name "C5") (class "Default")
      (node (ref "U11") (pin "6") (pinfunction "P0_5_6") (pintype "bidirectional"))
      (node (ref "U12") (pin "5") (pinfunction "QF_5") (pintype "output"))
      (node (ref "U14") (pin "5") (pinfunction "QF_5") (pintype "output"))
      (node (ref "U9") (pin "5") (pinfunction "QF_5") (pintype "output"))
    )
    (net (code "21") (name "C6") (class "Default")
      (node (ref "U11") (pin "7") (pinfunction "P0_6_7") (pintype "bidirectional"))
      (node (ref "U12") (pin "6") (pinfunction "QG_6") (pintype "output"))
      (node (ref "U14") (pin "6") (pinfunction "QG_6") (pintype "output"))
      (node (ref "U9") (pin "6") (pinfunction "QG_6") (pintype "output"))
    )
    (net (code "22") (name "C7") (class "Default")
      (node (ref "U11") (pin "8") (pinfunction "P0_7_8") (pintype "bidirectional"))
      (node (ref "U12") (pin "7") (pinfunction "QH_7") (pintype "output"))
      (node (ref "U14") (pin "7") (pinfunction "QH_7") (pintype "output"))
      (node (ref "U9") (pin "7") (pinfunction "QH_7") (pintype "output"))
    )
    (net (code "23") (name "C8") (class "Default")
      (node (ref "U10") (pin "15") (pinfunction "QA_15") (pintype "output"))
      (node (ref "U11") (pin "10") (pinfunction "P1_0_10") (pintype "bidirectional"))
      (node (ref "U13") (pin "15") (pinfunction "QA_15") (pintype "output"))
      (node (ref "U15") (pin "15") (pinfunction "QA_15") (pintype "output"))
    )
    (net (code "24") (name "C9") (class "Default")
      (node (ref "U10") (pin "1") (pinfunction "QB_1") (pintype "output"))
      (node (ref "U11") (pin "11") (pinfunction "P1_1_11") (pintype "bidirectional"))
      (node (ref "U13") (pin "1") (pinfunction "QB_1") (pintype "output"))
      (node (ref "U15") (pin "1") (pinfunction "QB_1") (pintype "output"))
    )
    (net (code "25") (name "C10") (class "Default")
      (node (ref "U10") (pin "2") (pinfunction "QC_2") (pintype "output"))
      (node (ref "U11") (pin "12") (pinfunction "P1_2_12") (pintype "bidirectional"))
      (node (ref "U13") (pin "2") (pinfunction "QC_2") (pintype "output"))
      (node (ref "U15") (pin "2") (pinfunction "QC_2") (pintype "output"))
    )
    (net (code "26") (name "C11") (class "Default")
      (node (ref "U10") (pin "3") (pinfunction "QD_3") (pintype "output"))
      (node (ref "U11") (pin "13") (pinfunction "P1_3_13") (pintype "bidirectional"))
      (node (ref "U13") (pin "3") (pinfunction "QD_3") (pintype "output"))
      (node (ref "U15") (pin "3") (pinfunction "QD_3") (pintype "output"))
    )
    (net (code "27") (name "C12") (class "Default")
      (node (ref "U10") (pin "4") (pinfunction "QE_4") (pintype "output"))
      (node (ref "U11") (pin "14") (pinfunction "P1_4_14") (pintype "bidirectional"))
      (node (ref "U13") (pin "4") (pinfunction "QE_4") (pintype "output"))
      (node (ref "U15") (pin "4") (pinfunction "QE_4") (pintype "output"))
    )
    (net (code "28") (name "C13") (class "Default")
      (node (ref "U10") (pin "5") (pinfunction "QF_5") (pintype "output"))
      (node (ref "U11") (pin "15") (pinfunction "P1_5_15") (pintype "bidirectional"))
      (node (ref "U13") (pin "5") (pinfunction "QF_5") (pintype "output"))
      (node (ref "U15") (pin "5") (pinfunction "QF_5") (pintype "output"))
    )
    (net (code "29") (name "C14") (class "Default")
      (node (ref "U10") (pin "6") (pinfunction "QG_6") (pintype "output"))
      (node (ref "U11") (pin "16") (pinfunction "P1_6_16") (pintype "bidirectional"))
      (node (ref "U13") (pin "6") (pinfunction "QG_6") (pintype "output"))
      (node (ref "U15") (pin "6") (pinfunction "QG_6") (pintype "output"))
    )
    (net (code "30") (name "C15") (class "Default")
      (node (ref "U10") (pin "7") (pinfunction "QH_7") (pintype "output"))
      (node (ref "U11") (pin "17") (pinfunction "P1_7_17") (pintype "bidirectional"))
      (node (ref "U13") (pin "7") (pinfunction "QH_7") (pintype "output"))
      (node (ref "U15") (pin "7") (pinfunction "QH_7") (pintype "output"))
    )
    (net (code "31") (name "COUNT_EN1") (class "Default")
      (node (ref "U10") (pin "14") (pinfunction "~{OE}_14") (pintype "input"))
      (node (ref "U25") (pin "4") (pinfunction "P0_3_4") (pintype "bidirectional"))
      (node (ref "U9") (pin "14") (pinfunction "~{OE}_14") (pintype "input"))
    )
    (net (code "32") (name "COUNT_EN2") (class "Default")
      (node (ref "U12") (pin "14") (pinfunction "~{OE}_14") (pintype "input"))
      (node (ref "U13") (pin "14") (pinfunction "~{OE}_14") (pintype "input"))
      (node (ref "U25") (pin "5") (pinfunction "P0_4_5") (pintype "bidirectional"))
    )
    (net (code "33") (name "COUNT_EN3") (class "Default")
      (node (ref "U14") (pin "14") (pinfunction "~{OE}_14") (pintype "input"))
      (node (ref "U15") (pin "14") (pinfunction "~{OE}_14") (pintype "input"))
      (node (ref "U25") (pin "6") (pinfunction "P0_5_6") (pintype "bidirectional"))
    )
    (net (code "34") (name "D1") (class "Default")
      (node (ref "D1") (pin "2") (pinfunction "C_2") (pintype "passive"))
      (node (ref "J1") (pin "5") (pinfunction "DIGITAL_5") (pintype "passive"))
      (node (ref "R13") (pin "2") (pinfunction "2_2") (pintype "passive"))
      (node (ref "R25") (pin "1") (pinfunction "1_1") (pintype "passive"))
    )
    (net (code "35") (name "D1_SENSE") (class "Default")
      (node (ref "R25") (pin "2") (pinfunction "2_2") (pintype "passive"))
      (node (ref "U17") (pin "4") (pinfunction "INP_4") (pintype "input"))
      (node (ref "U25") (pin "12") (pinfunction "P1_2_12") (pintype "bidirectional"))
    )
    (net (code "36") (name "D2") (class "Default")
      (node (ref "D3") (pin "2") (pinfunction "C_2") (pintype "passive"))
      (node (ref "J2") (pin "5") (pinfunction "DIGITAL_5") (pintype "passive"))
      (node (ref "R23") (pin "2") (pinfunction "2_2") (pintype "passive"))
      (node (ref "R26") (pin "1") (pinfunction "1_1") (pintype "passive"))
    )
    (net (code "37") (name "D2_SENSE") (class "Default")
      (node (ref "R26") (pin "2") (pinfunction "2_2") (pintype "passive"))
      (node (ref "U20") (pin "4") (pinfunction "INP_4") (pintype "input"))
      (node (ref "U25") (pin "13") (pinfunction "P1_3_13") (pintype "bidirectional"))
    )
    (net (code "38") (name "D3") (class "Default")
      (node (ref "D5") (pin "2") (pinfunction "C_2") (pintype "passive"))
      (node (ref "J3") (pin "5") (pinfunction "DIGITAL_5") (pintype "passive"))
      (node (ref "R24") (pin "2") (pinfunction "2_2") (pintype "passive"))
      (node (ref "R27") (pin "1") (pinfunction "1_1") (pintype "passive"))
    )
    (net (code "39") (name "D3_SENSE") (class "Default")
      (node (ref "R27") (pin "2") (pinfunction "2_2") (pintype "passive"))
      (node (ref "U23") (pin "4") (pinfunction "INP_4") (pintype "input"))
      (node (ref "U25") (pin "14") (pinfunction "P1_4_14") (pintype "bidirectional"))
    )
    (net (code "40") (name "GND") (class "Default")
      (node (ref "C1") (pin "2") (pinfunction "2_2") (pintype "passive"))
      (node (ref "C10") (pin "2") (pinfunction "2_2") (pintype "passive"))
      (node (ref "C11") (pin "2") (pinfunction "2_2") (pintype "passive"))
      (node (ref "C12") (pin "2") (pinfunction "2_2") (pintype "passive"))
      (node (ref "C13") (pin "2") (pinfunction "2_2") (pintype "passive"))
      (node (ref "C14") (pin "2") (pinfunction "2_2") (pintype "passive"))
      (node (ref "C15") (pin "2") (pinfunction "2_2") (pintype "passive"))
      (node (ref "C16") (pin "2") (pinfunction "2_2") (pintype "passive"))
      (node (ref "C17") (pin "2") (pinfunction "2_2") (pintype "passive"))
      (node (ref "C18") (pin "2") (pinfunction "2_2") (pintype "passive"))
      (node (ref "C19") (pin "2") (pinfunction "2_2") (pintype "passive"))
      (node (ref "C2") (pin "2") (pinfunction "2_2") (pintype "passive"))
      (node (ref "C20") (pin "2") (pinfunction "2_2") (pintype "passive"))
      (node (ref "C22") (pin "2") (pinfunction "2_2") (pintype "passive"))
      (node (ref "C23") (pin "2") (pinfunction "2_2") (pintype "passive"))
      (node (ref "C3") (pin "2") (pinfunction "2_2") (pintype "passive"))
      (node (ref "C4") (pin "2") (pinfunction "2_2") (pintype "passive"))
      (node (ref "C5") (pin "2") (pinfunction "2_2") (pintype "passive"))
      (node (ref "C6") (pin "2") (pinfunction "2_2") (pintype "passive"))
      (node (ref "C7") (pin "2") (pinfunction "2_2") (pintype "passive"))
      (node (ref "C8") (pin "2") (pinfunction "2_2") (pintype "passive"))
      (node (ref "C9") (pin "2") (pinfunction "2_2") (pintype "passive"))
      (node (ref "D1") (pin "1") (pinfunction "A_1") (pintype "passive"))
      (node (ref "D2") (pin "1") (pinfunction "A_1") (pintype "passive"))
      (node (ref "D3") (pin "1") (pinfunction "A_1") (pintype "passive"))
      (node (ref "D4") (pin "1") (pinfunction "A_1") (pintype "passive"))
      (node (ref "D5") (pin "1") (pinfunction "A_1") (pintype "passive"))
      (node (ref "D6") (pin "1") (pinfunction "A_1") (pintype "passive"))
      (node (ref "J1") (pin "3") (pinfunction "GND_3") (pintype "passive"))
      (node (ref "J2") (pin "3") (pinfunction "GND_3") (pintype "passive"))
      (node (ref "J3") (pin "3") (pinfunction "GND_3") (pintype "passive"))
      (node (ref "J4") (pin "1") (pinfunction "GND_1") (pintype "passive"))
      (node (ref "Q1") (pin "2") (pinfunction "S_2") (pintype "bidirectional"))
      (node (ref "Q2") (pin "2") (pinfunction "S_2") (pintype "bidirectional"))
      (node (ref "Q3") (pin "2") (pinfunction "S_2") (pintype "bidirectional"))
      (node (ref "R10") (pin "1") (pinfunction "1_1") (pintype "passive"))
      (node (ref "R11") (pin "1") (pinfunction "1_1") (pintype "passive"))
      (node (ref "R13") (pin "1") (pinfunction "1_1") (pintype "passive"))
      (node (ref "R23") (pin "1") (pinfunction "1_1") (pintype "passive"))
      (node (ref "R24") (pin "1") (pinfunction "1_1") (pintype "passive"))
      (node (ref "U1") (pin "3") (pinfunction "GND_3") (pintype "power_in"))
      (node (ref "U10") (pin "12") (pinfunction "~{CCKEN}_12") (pintype "input"))
      (node (ref "U10") (pin "8") (pinfunction "GND_8") (pintype "power_in"))
      (node (ref "U10") (pin "EP") (pinfunction "GND_EP") (pintype "power_in"))
      (node (ref "U11") (pin "18") (pinfunction "A0_18") (pintype "input"))
      (node (ref "U11") (pin "23") (pinfunction "A1_23") (pintype "input"))
      (node (ref "U11") (pin "9") (pinfunction "VSS_9") (pintype "power_in"))
      (node (ref "U11") (pin "EP") (pinfunction "VSS_EP") (pintype "power_in"))
      (node (ref "U12") (pin "12") (pinfunction "~{CCKEN}_12") (pintype "input"))
      (node (ref "U12") (pin "8") (pinfunction "GND_8") (pintype "power_in"))
      (node (ref "U12") (pin "EP") (pinfunction "GND_EP") (pintype "power_in"))
      (node (ref "U13") (pin "12") (pinfunction "~{CCKEN}_12") (pintype "input"))
      (node (ref "U13") (pin "8") (pinfunction "GND_8") (pintype "power_in"))
      (node (ref "U13") (pin "EP") (pinfunction "GND_EP") (pintype "power_in"))
      (node (ref "U14") (pin "12") (pinfunction "~{CCKEN}_12") (pintype "input"))
      (node (ref "U14") (pin "8") (pinfunction "GND_8") (pintype "power_in"))
      (node (ref "U14") (pin "EP") (pinfunction "GND_EP") (pintype "power_in"))
      (node (ref "U15") (pin "12") (pinfunction "~{CCKEN}_12") (pintype "input"))
      (node (ref "U15") (pin "8") (pinfunction "GND_8") (pintype "power_in"))
      (node (ref "U15") (pin "EP") (pinfunction "GND_EP") (pintype "power_in"))
      (node (ref "U16") (pin "2") (pinfunction "GND_2") (pintype "power_in"))
      (node (ref "U16") (pin "3") (pinfunction "GND_3") (pintype "power_in"))
      (node (ref "U17") (pin "2") (pinfunction "GND_2") (pintype "power_in"))
      (node (ref "U17") (pin "3") (pinfunction "GND_3") (pintype "power_in"))
      (node (ref "U18") (pin "3") (pinfunction "GND_3") (pintype "power_in"))
      (node (ref "U19") (pin "2") (pinfunction "GND_2") (pintype "power_in"))
      (node (ref "U19") (pin "3") (pinfunction "GND_3") (pintype "power_in"))
      (node (ref "U2") (pin "4") (pinfunction "GND_4") (pintype "power_in"))
      (node (ref "U20") (pin "2") (pinfunction "GND_2") (pintype "power_in"))
      (node (ref "U20") (pin "3") (pinfunction "GND_3") (pintype "power_in"))
      (node (ref "U21") (pin "3") (pinfunction "GND_3") (pintype "power_in"))
      (node (ref "U22") (pin "2") (pinfunction "GND_2") (pintype "power_in"))
      (node (ref "U22") (pin "3") (pinfunction "GND_3") (pintype "power_in"))
      (node (ref "U23") (pin "2") (pinfunction "GND_2") (pintype "power_in"))
      (node (ref "U23") (pin "3") (pinfunction "GND_3") (pintype "power_in"))
      (node (ref "U24") (pin "3") (pinfunction "GND_3") (pintype "power_in"))
      (node (ref "U25") (pin "24") (pinfunction "A2_24") (pintype "input"))
      (node (ref "U25") (pin "9") (pinfunction "VSS_9") (pintype "power_in"))
      (node (ref "U25") (pin "EP") (pinfunction "VSS_EP") (pintype "power_in"))
      (node (ref "U26") (pin "18") (pinfunction "A0_18") (pintype "input"))
      (node (ref "U26") (pin "23") (pinfunction "A1_23") (pintype "input"))
      (node (ref "U26") (pin "24") (pinfunction "A2_24") (pintype "input"))
      (node (ref "U26") (pin "9") (pinfunction "VSS_9") (pintype "power_in"))
      (node (ref "U26") (pin "EP") (pinfunction "VSS_EP") (pintype "power_in"))
      (node (ref "U28") (pin "4") (pinfunction "AGND_4") (pintype "power_in"))
      (node (ref "U28") (pin "8") (pinfunction "PGND_8") (pintype "power_in"))
      (node (ref "U3") (pin "2") (pinfunction "GND_2") (pintype "power_in"))
      (node (ref "U4") (pin "2") (pinfunction "GND_2") (pintype "power_in"))
      (node (ref "U5") (pin "2") (pinfunction "GND_2") (pintype "power_in"))
      (node (ref "U6") (pin "2") (pinfunction "GND_2") (pintype "power_in"))
      (node (ref "U6") (pin "5") (pinfunction "WP_5") (pintype "input"))
      (node (ref "U7") (pin "8") (pinfunction "GND_8") (pintype "power_in"))
      (node (ref "U7") (pin "EP") (pinfunction "GND_EP") (pintype "power_in"))
      (node (ref "U8") (pin "2") (pinfunction "GND_2") (pintype "power_in"))
      (node (ref "U9") (pin "12") (pinfunction "~{CCKEN}_12") (pintype "input"))
      (node (ref "U9") (pin "8") (pinfunction "GND_8") (pintype "power_in"))
      (node (ref "U9") (pin "EP") (pinfunction "GND_EP") (pintype "power_in"))
    )
    (net (code "41") (name "GPIOA") (class "Default")
      (node (ref "J4") (pin "6") (pinfunction "RX_6") (pintype "passive"))
      (node (ref "R29") (pin "1") (pinfunction "1_1") (pintype "passive"))
      (node (ref "U26") (pin "22") (pinfunction "~{INT}_22") (pintype "output"))
    )
    (net (code "42") (name "GPIOB") (class "Default")
      (node (ref "J4") (pin "5") (pinfunction "TX_5") (pintype "passive"))
      (node (ref "R28") (pin "1") (pinfunction "1_1") (pintype "passive"))
      (node (ref "U25") (pin "22") (pinfunction "~{INT}_22") (pintype "output"))
    )
    (net (code "43") (name "LOAD") (class "Default")
      (node (ref "U10") (pin "13") (pinfunction "RCLK_13") (pintype "input"))
      (node (ref "U12") (pin "13") (pinfunction "RCLK_13") (pintype "input"))
      (node (ref "U13") (pin "13") (pinfunction "RCLK_13") (pintype "input"))
      (node (ref "U14") (pin "13") (pinfunction "RCLK_13") (pintype "input"))
      (node (ref "U15") (pin "13") (pinfunction "RCLK_13") (pintype "input"))
      (node (ref "U25") (pin "7") (pinfunction "P0_6_7") (pintype "bidirectional"))
      (node (ref "U9") (pin "13") (pinfunction "RCLK_13") (pintype "input"))
    )
    (net (code "44") (name "MUX_EN") (class "Default")
      (node (ref "R6") (pin "1") (pinfunction "1_1") (pintype "passive"))
      (node (ref "U26") (pin "13") (pinfunction "P1_3_13") (pintype "bidirectional"))
      (node (ref "U7") (pin "6") (pinfunction "~{E}_6") (pintype "input"))
    )
    (net (code "45") (name "MUX_SEL0") (class "Default")
      (node (ref "R7") (pin "1") (pinfunction "1_1") (pintype "passive"))
      (node (ref "U26") (pin "10") (pinfunction "P1_0_10") (pintype "bidirectional"))
      (node (ref "U7") (pin "10") (pinfunction "S0_10") (pintype "input"))
    )
    (net (code "46") (name "MUX_SEL1") (class "Default")
      (node (ref "R8") (pin "1") (pinfunction "1_1") (pintype "passive"))
      (node (ref "U26") (pin "11") (pinfunction "P1_1_11") (pintype "bidirectional"))
      (node (ref "U7") (pin "9") (pinfunction "S1_9") (pintype "input"))
    )
    (net (code "47") (name "MUX_SEL2") (class "Default")
      (node (ref "R9") (pin "1") (pinfunction "1_1") (pintype "passive"))
      (node (ref "U26") (pin "12") (pinfunction "P1_2_12") (pintype "bidirectional"))
      (node (ref "U8") (pin "6") (pinfunction "S_6") (pintype "input"))
    )
    (net (code "48") (name "Net-(L2-2)") (class "Default")
      (node (ref "L2") (pin "P$2") (pinfunction "2_P$2") (pintype "passive"))
      (node (ref "U28") (pin "1") (pinfunction "LX_1") (pintype "power_in"))
    )
    (net (code "49") (name "Net-(Q1-D)") (class "Default")
      (node (ref "Q1") (pin "3") (pinfunction "D_3") (pintype "bidirectional"))
      (node (ref "R20") (pin "1") (pinfunction "1_1") (pintype "passive"))
    )
    (net (code "50") (name "Net-(Q2-D)") (class "Default")
      (node (ref "Q2") (pin "3") (pinfunction "D_3") (pintype "bidirectional"))
      (node (ref "R21") (pin "1") (pinfunction "1_1") (pintype "passive"))
    )
    (net (code "51") (name "Net-(Q3-D)") (class "Default")
      (node (ref "Q3") (pin "3") (pinfunction "D_3") (pintype "bidirectional"))
      (node (ref "R22") (pin "1") (pinfunction "1_1") (pintype "passive"))
    )
    (net (code "52") (name "Net-(U7-1Z)") (class "Default")
      (node (ref "U7") (pin "13") (pinfunction "1Z_13") (pintype "output"))
      (node (ref "U8") (pin "1") (pinfunction "B2_1") (pintype "bidirectional"))
    )
    (net (code "53") (name "Net-(U7-2Z)") (class "Default")
      (node (ref "U7") (pin "3") (pinfunction "2Z_3") (pintype "output"))
      (node (ref "U8") (pin "3") (pinfunction "B1_3") (pintype "bidirectional"))
    )
    (net (code "54") (name "Net-(U10-CCLK)") (class "Default")
      (node (ref "U10") (pin "11") (pinfunction "CCLK_11") (pintype "input"))
      (node (ref "U9") (pin "9") (pinfunction "~{RCO}_9") (pintype "output"))
    )
    (net (code "55") (name "Net-(U12-~{RCO})") (class "Default")
      (node (ref "U12") (pin "9") (pinfunction "~{RCO}_9") (pintype "output"))
      (node (ref "U13") (pin "11") (pinfunction "CCLK_11") (pintype "input"))
    )
    (net (code "56") (name "Net-(U14-~{RCO})") (class "Default")
      (node (ref "U14") (pin "9") (pinfunction "~{RCO}_9") (pintype "output"))
      (node (ref "U15") (pin "11") (pinfunction "CCLK_11") (pintype "input"))
    )
    (net (code "57") (name "Net-(U16-OUT)") (class "Default")
      (node (ref "U16") (pin "5") (pinfunction "OUT_5") (pintype "output"))
      (node (ref "U18") (pin "1") (pinfunction "A_1") (pintype "input"))
    )
    (net (code "58") (name "Net-(U17-OUT)") (class "Default")
      (node (ref "U17") (pin "5") (pinfunction "OUT_5") (pintype "output"))
      (node (ref "U18") (pin "2") (pinfunction "B_2") (pintype "input"))
    )
    (net (code "59") (name "Net-(U18-Y)") (class "Default")
      (node (ref "R14") (pin "1") (pinfunction "1_1") (pintype "passive"))
      (node (ref "U18") (pin "4") (pinfunction "Y_4") (pintype "output"))
    )
    (net (code "60") (name "Net-(U19-OUT)") (class "Default")
      (node (ref "U19") (pin "5") (pinfunction "OUT_5") (pintype "output"))
      (node (ref "U21") (pin "1") (pinfunction "A_1") (pintype "input"))
    )
    (net (code "61") (name "Net-(U20-OUT)") (class "Default")
      (node (ref "U20") (pin "5") (pinfunction "OUT_5") (pintype "output"))
      (node (ref "U21") (pin "2") (pinfunction "B_2") (pintype "input"))
    )
    (net (code "62") (name "Net-(U21-Y)") (class "Default")
      (node (ref "R15") (pin "1") (pinfunction "1_1") (pintype "passive"))
      (node (ref "U21") (pin "4") (pinfunction "Y_4") (pintype "output"))
    )
    (net (code "63") (name "Net-(U22-OUT)") (class "Default")
      (node (ref "U22") (pin "5") (pinfunction "OUT_5") (pintype "output"))
      (node (ref "U24") (pin "1") (pinfunction "A_1") (pintype "input"))
    )
    (net (code "64") (name "Net-(U23-OUT)") (class "Default")
      (node (ref "U23") (pin "5") (pinfunction "OUT_5") (pintype "output"))
      (node (ref "U24") (pin "2") (pinfunction "B_2") (pintype "input"))
    )
    (net (code "65") (name "Net-(U24-Y)") (class "Default")
      (node (ref "R19") (pin "1") (pinfunction "1_1") (pintype "passive"))
      (node (ref "U24") (pin "4") (pinfunction "Y_4") (pintype "output"))
    )
    (net (code "66") (name "Net-(U28-FB)") (class "Default")
      (node (ref "C21") (pin "2") (pinfunction "2_2") (pintype "passive"))
      (node (ref "R11") (pin "2") (pinfunction "2_2") (pintype "passive"))
      (node (ref "R12") (pin "1") (pinfunction "1_1") (pintype "passive"))
      (node (ref "U28") (pin "5") (pinfunction "FB_5") (pintype "input"))
    )
    (net (code "67") (name "Net-(U28-RSET)") (class "Default")
      (node (ref "R10") (pin "2") (pinfunction "2_2") (pintype "passive"))
      (node (ref "U28") (pin "6") (pinfunction "RSET_6") (pintype "input"))
    )
    (net (code "68") (name "OD1") (class "Default")
      (node (ref "C11") (pin "1") (pinfunction "1_1") (pintype "passive"))
      (node (ref "D2") (pin "2") (pinfunction "C_2") (pintype "passive"))
      (node (ref "J1") (pin "2") (pinfunction "DIGITAL_OPENDRAIN_2") (pintype "passive"))
      (node (ref "R16") (pin "1") (pinfunction "1_1") (pintype "passive"))
      (node (ref "U16") (pin "4") (pinfunction "INP_4") (pintype "input"))
      (node (ref "U25") (pin "15") (pinfunction "P1_5_15") (pintype "bidirectional"))
    )
    (net (code "69") (name "OD2") (class "Default")
      (node (ref "C10") (pin "1") (pinfunction "1_1") (pintype "passive"))
      (node (ref "D4") (pin "2") (pinfunction "C_2") (pintype "passive"))
      (node (ref "J2") (pin "2") (pinfunction "DIGITAL_OPENDRAIN_2") (pintype "passive"))
      (node (ref "R17") (pin "1") (pinfunction "1_1") (pintype "passive"))
      (node (ref "U19") (pin "4") (pinfunction "INP_4") (pintype "input"))
      (node (ref "U25") (pin "16") (pinfunction "P1_6_16") (pintype "bidirectional"))
    )
    (net (code "70") (name "OD3") (class "Default")
      (node (ref "C9") (pin "1") (pinfunction "1_1") (pintype "passive"))
      (node (ref "D6") (pin "2") (pinfunction "C_2") (pintype "passive"))
      (node (ref "J3") (pin "2") (pinfunction "DIGITAL_OPENDRAIN_2") (pintype "passive"))
      (node (ref "R18") (pin "1") (pinfunction "1_1") (pintype "passive"))
      (node (ref "U22") (pin "4") (pinfunction "INP_4") (pintype "input"))
      (node (ref "U25") (pin "17") (pinfunction "P1_7_17") (pintype "bidirectional"))
    )
    (net (code "71") (name "OUT1") (class "Default")
      (node (ref "R14") (pin "2") (pinfunction "2_2") (pintype "passive"))
      (node (ref "U25") (pin "1") (pinfunction "P0_0_1") (pintype "bidirectional"))
      (node (ref "U9") (pin "11") (pinfunction "CCLK_11") (pintype "input"))
    )
    (net (code "72") (name "OUT2") (class "Default")
      (node (ref "R15") (pin "2") (pinfunction "2_2") (pintype "passive"))
      (node (ref "U12") (pin "11") (pinfunction "CCLK_11") (pintype "input"))
      (node (ref "U25") (pin "2") (pinfunction "P0_1_2") (pintype "bidirectional"))
    )
    (net (code "73") (name "OUT3") (class "Default")
      (node (ref "R19") (pin "2") (pinfunction "2_2") (pintype "passive"))
      (node (ref "U14") (pin "11") (pinfunction "CCLK_11") (pintype "input"))
      (node (ref "U25") (pin "3") (pinfunction "P0_2_3") (pintype "bidirectional"))
    )
    (net (code "74") (name "PORT1_EN") (class "Default")
      (node (ref "U26") (pin "2") (pinfunction "P0_1_2") (pintype "bidirectional"))
      (node (ref "U3") (pin "3") (pinfunction "EN_3") (pintype "input"))
    )
    (net (code "75") (name "PORT2_EN") (class "Default")
      (node (ref "U26") (pin "4") (pinfunction "P0_3_4") (pintype "bidirectional"))
      (node (ref "U4") (pin "3") (pinfunction "EN_3") (pintype "input"))
    )
    (net (code "76") (name "PORT3_EN") (class "Default")
      (node (ref "U26") (pin "6") (pinfunction "P0_5_6") (pintype "bidirectional"))
      (node (ref "U5") (pin "3") (pinfunction "EN_3") (pintype "input"))
    )
    (net (code "77") (name "SCL") (class "Default")
      (node (ref "J4") (pin "4") (pinfunction "SCL_4") (pintype "passive"))
      (node (ref "R2") (pin "1") (pinfunction "1_1") (pintype "passive"))
      (node (ref "U11") (pin "19") (pinfunction "SCL_19") (pintype "input"))
      (node (ref "U2") (pin "2") (pinfunction "A1_2") (pintype "bidirectional"))
      (node (ref "U25") (pin "19") (pinfunction "SCL_19") (pintype "input"))
      (node (ref "U26") (pin "19") (pinfunction "SCL_19") (pintype "input"))
      (node (ref "U6") (pin "1") (pinfunction "SCL_1") (pintype "input"))
    )
    (net (code "78") (name "SCL_HV") (class "Default")
      (node (ref "U1") (pin "10") (pinfunction "SCL_10") (pintype "input"))
      (node (ref "U2") (pin "7") (pinfunction "B1_7") (pintype "bidirectional"))
    )
    (net (code "79") (name "SDA") (class "Default")
      (node (ref "J4") (pin "3") (pinfunction "SDA_3") (pintype "passive"))
      (node (ref "R1") (pin "1") (pinfunction "1_1") (pintype "passive"))
      (node (ref "U11") (pin "20") (pinfunction "SDA_20") (pintype "bidirectional"))
      (node (ref "U2") (pin "3") (pinfunction "A2_3") (pintype "bidirectional"))
      (node (ref "U25") (pin "20") (pinfunction "SDA_20") (pintype "bidirectional"))
      (node (ref "U26") (pin "20") (pinfunction "SDA_20") (pintype "bidirectional"))
      (node (ref "U6") (pin "3") (pinfunction "SDA_3") (pintype "bidirectional"))
    )
    (net (code "80") (name "SDA_HV") (class "Default")
      (node (ref "U1") (pin "9") (pinfunction "SDA_9") (pintype "bidirectional"))
      (node (ref "U2") (pin "6") (pinfunction "B2_6") (pintype "bidirectional"))
    )
    (net (code "81") (name "VMUX") (class "Default")
      (node (ref "D7") (pin "3") (pinfunction "C_3") (pintype "passive"))
      (node (ref "R6") (pin "2") (pinfunction "2_2") (pintype "passive"))
      (node (ref "R7") (pin "2") (pinfunction "2_2") (pintype "passive"))
      (node (ref "R8") (pin "2") (pinfunction "2_2") (pintype "passive"))
      (node (ref "R9") (pin "2") (pinfunction "2_2") (pintype "passive"))
      (node (ref "U7") (pin "16") (pinfunction "VCC_16") (pintype "power_in"))
      (node (ref "U8") (pin "5") (pinfunction "VCC_5") (pintype "power_in"))
    )
    (net (code "82") (name "VPORT1_IN") (class "Default")
      (node (ref "C12") (pin "1") (pinfunction "1_1") (pintype "passive"))
      (node (ref "S1") (pin "2") (pinfunction "P_2") (pintype "passive"))
      (node (ref "U3") (pin "1") (pinfunction "VIN_1") (pintype "power_in"))
      (node (ref "U7") (pin "12") (pinfunction "1Y0_12") (pintype "input"))
    )
    (net (code "83") (name "VPORT1_OUT") (class "Default")
      (node (ref "C13") (pin "1") (pinfunction "1_1") (pintype "passive"))
      (node (ref "J1") (pin "1") (pinfunction "3V3_1") (pintype "passive"))
      (node (ref "U3") (pin "5") (pinfunction "VOUT_5") (pintype "power_in"))
      (node (ref "U7") (pin "1") (pinfunction "2Y0_1") (pintype "input"))
    )
    (net (code "84") (name "VPORT2_IN") (class "Default")
      (node (ref "C17") (pin "1") (pinfunction "1_1") (pintype "passive"))
      (node (ref "S2") (pin "2") (pinfunction "P_2") (pintype "passive"))
      (node (ref "U4") (pin "1") (pinfunction "VIN_1") (pintype "power_in"))
      (node (ref "U7") (pin "14") (pinfunction "1Y1_14") (pintype "input"))
    )
    (net (code "85") (name "VPORT2_OUT") (class "Default")
      (node (ref "C18") (pin "1") (pinfunction "1_1") (pintype "passive"))
      (node (ref "J2") (pin "1") (pinfunction "3V3_1") (pintype "passive"))
      (node (ref "U4") (pin "5") (pinfunction "VOUT_5") (pintype "power_in"))
      (node (ref "U7") (pin "5") (pinfunction "2Y1_5") (pintype "input"))
    )
    (net (code "86") (name "VPORT3_IN") (class "Default")
      (node (ref "C19") (pin "1") (pinfunction "1_1") (pintype "passive"))
      (node (ref "S3") (pin "2") (pinfunction "P_2") (pintype "passive"))
      (node (ref "U5") (pin "1") (pinfunction "VIN_1") (pintype "power_in"))
      (node (ref "U7") (pin "15") (pinfunction "1Y2_15") (pintype "input"))
    )
    (net (code "87") (name "VPORT3_OUT") (class "Default")
      (node (ref "C20") (pin "1") (pinfunction "1_1") (pintype "passive"))
      (node (ref "J3") (pin "1") (pinfunction "3V3_1") (pintype "passive"))
      (node (ref "U5") (pin "5") (pinfunction "VOUT_5") (pintype "power_in"))
      (node (ref "U7") (pin "2") (pinfunction "2Y2_2") (pintype "input"))
    )
    (net (code "88") (name "unconnected-(U7-2Y3-Pad4)") (class "Default")
      (node (ref "U7") (pin "4") (pinfunction "2Y3_4") (pintype "input"))
    )
    (net (code "89") (name "unconnected-(U11-~{INT}-Pad22)") (class "Default")
      (node (ref "U11") (pin "22") (pinfunction "~{INT}_22") (pintype "output"))
    )
    (net (code "90") (name "~{OVF1}") (class "Default")
      (node (ref "U10") (pin "9") (pinfunction "~{RCO}_9") (pintype "output"))
      (node (ref "U25") (pin "8") (pinfunction "P0_7_8") (pintype "bidirectional"))
    )
    (net (code "91") (name "~{OVF2}") (class "Default")
      (node (ref "U13") (pin "9") (pinfunction "~{RCO}_9") (pintype "output"))
      (node (ref "U25") (pin "10") (pinfunction "P1_0_10") (pintype "bidirectional"))
    )
    (net (code "92") (name "~{OVF3}") (class "Default")
      (node (ref "U15") (pin "9") (pinfunction "~{RCO}_9") (pintype "output"))
      (node (ref "U25") (pin "11") (pinfunction "P1_1_11") (pintype "bidirectional"))
    )
    (net (code "93") (name "~{PORT1_FAULT}") (class "Default")
      (node (ref "U26") (pin "1") (pinfunction "P0_0_1") (pintype "bidirectional"))
      (node (ref "U3") (pin "4") (pinfunction "~{FAULT}_4") (pintype "output"))
    )
    (net (code "94") (name "~{PORT2_FAULT}") (class "Default")
      (node (ref "U26") (pin "3") (pinfunction "P0_2_3") (pintype "bidirectional"))
      (node (ref "U4") (pin "4") (pinfunction "~{FAULT}_4") (pintype "output"))
    )
    (net (code "95") (name "~{PORT3_FAULT}") (class "Default")
      (node (ref "U26") (pin "5") (pinfunction "P0_4_5") (pintype "bidirectional"))
      (node (ref "U5") (pin "4") (pinfunction "~{FAULT}_4") (pintype "output"))
    )
    (net (code "96") (name "~{RST}") (class "Default")
      (node (ref "U10") (pin "10") (pinfunction "~{CCLR}_10") (pintype "input"))
      (node (ref "U12") (pin "10") (pinfunction "~{CCLR}_10") (pintype "input"))
      (node (ref "U13") (pin "10") (pinfunction "~{CCLR}_10") (pintype "input"))
      (node (ref "U14") (pin "10") (pinfunction "~{CCLR}_10") (pintype "input"))
      (node (ref "U15") (pin "10") (pinfunction "~{CCLR}_10") (pintype "input"))
      (node (ref "U26") (pin "7") (pinfunction "P0_6_7") (pintype "bidirectional"))
      (node (ref "U9") (pin "10") (pinfunction "~{CCLR}_10") (pintype "input"))
    )
  )
)
